# scehmatic1.net
KiCad netlist of a schematic drawn in EAGLE
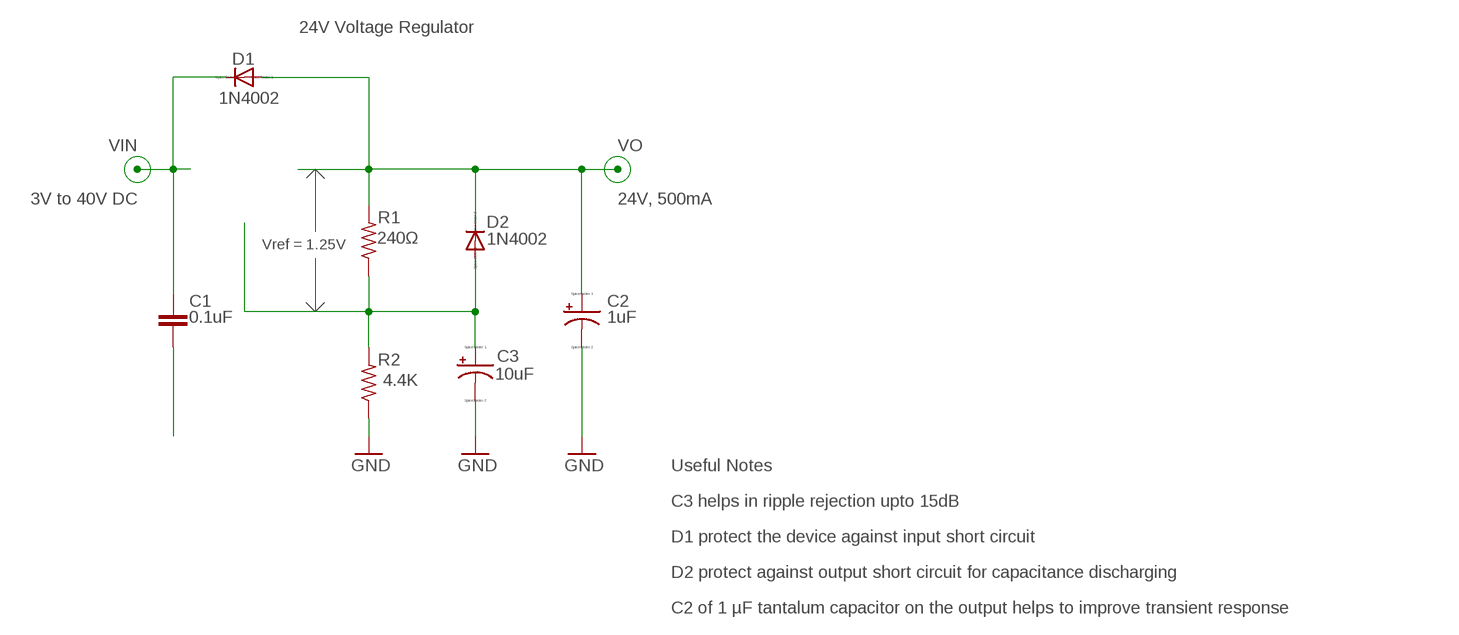
[diagram p0: schematic, sheet 1]

(export (version "E")
  (design (tool "Eeschema 10.0.6"))
  (components
    (comp (ref "C1")
      (value "0.1uF")
      (footprint "eagle-import:C075-052X106")
      (libsource (lib "eagle-import") (part "C-EU075-052X106"))
    )
    (comp (ref "C2")
      (value "1uF")
      (footprint "eagle-import:085CS_1AR")
      (libsource (lib "eagle-import") (part "CPOL-US085CS-1AR"))
    )
    (comp (ref "C3")
      (value "10uF")
      (footprint "eagle-import:085CS_1AR")
      (libsource (lib "eagle-import") (part "CPOL-US085CS-1AR"))
    )
    (comp (ref "D1")
      (value "1N4002")
      (footprint "eagle-import:DO41-10")
      (libsource (lib "eagle-import") (part "1N4004"))
    )
    (comp (ref "D2")
      (value "1N4002")
      (footprint "eagle-import:DO41-10")
      (libsource (lib "eagle-import") (part "1N4004"))
    )
    (comp (ref "R1")
      (value "240Ω")
      (footprint "eagle-import:M0805")
      (libsource (lib "eagle-import") (part "R-US_M0805"))
    )
    (comp (ref "R2")
      (value "4.4K")
      (footprint "eagle-import:M0805")
      (libsource (lib "eagle-import") (part "R-US_M0805"))
    )
  )
  (nets
    (net (code "1") (name "/VIN") (class "Default")
      (node (ref "C1") (pin "1") (pinfunction "1_1") (pintype "passive"))
      (node (ref "D1") (pin "C") (pinfunction "C_C") (pintype "passive"))
    )
    (net (code "2") (name "/VO") (class "Default")
      (node (ref "C2") (pin "+") (pinfunction "+_+") (pintype "passive"))
      (node (ref "D1") (pin "A") (pinfunction "A_A") (pintype "passive"))
      (node (ref "D2") (pin "C") (pinfunction "C_C") (pintype "passive"))
      (node (ref "R1") (pin "2") (pinfunction "2_2") (pintype "passive"))
    )
    (net (code "3") (name "GND") (class "Default")
      (node (ref "C2") (pin "-") (pinfunction "-_-") (pintype "passive"))
      (node (ref "C3") (pin "-") (pinfunction "-_-") (pintype "passive"))
      (node (ref "R2") (pin "1") (pinfunction "1_1") (pintype "passive"))
    )
    (net (code "4") (name "Net-(C3-Pad+)") (class "Default")
      (node (ref "C3") (pin "+") (pinfunction "+_+") (pintype "passive"))
      (node (ref "D2") (pin "A") (pinfunction "A_A") (pintype "passive"))
      (node (ref "R1") (pin "1") (pinfunction "1_1") (pintype "passive"))
      (node (ref "R2") (pin "2") (pinfunction "2_2") (pintype "passive"))
    )
    (net (code "5") (name "unconnected-(C1-Pad2)") (class "Default")
      (node (ref "C1") (pin "2") (pinfunction "2_2") (pintype "passive"))
    )
  )
)
